# P2B14-001.net
KiCad netlist of a schematic drawn in EAGLE
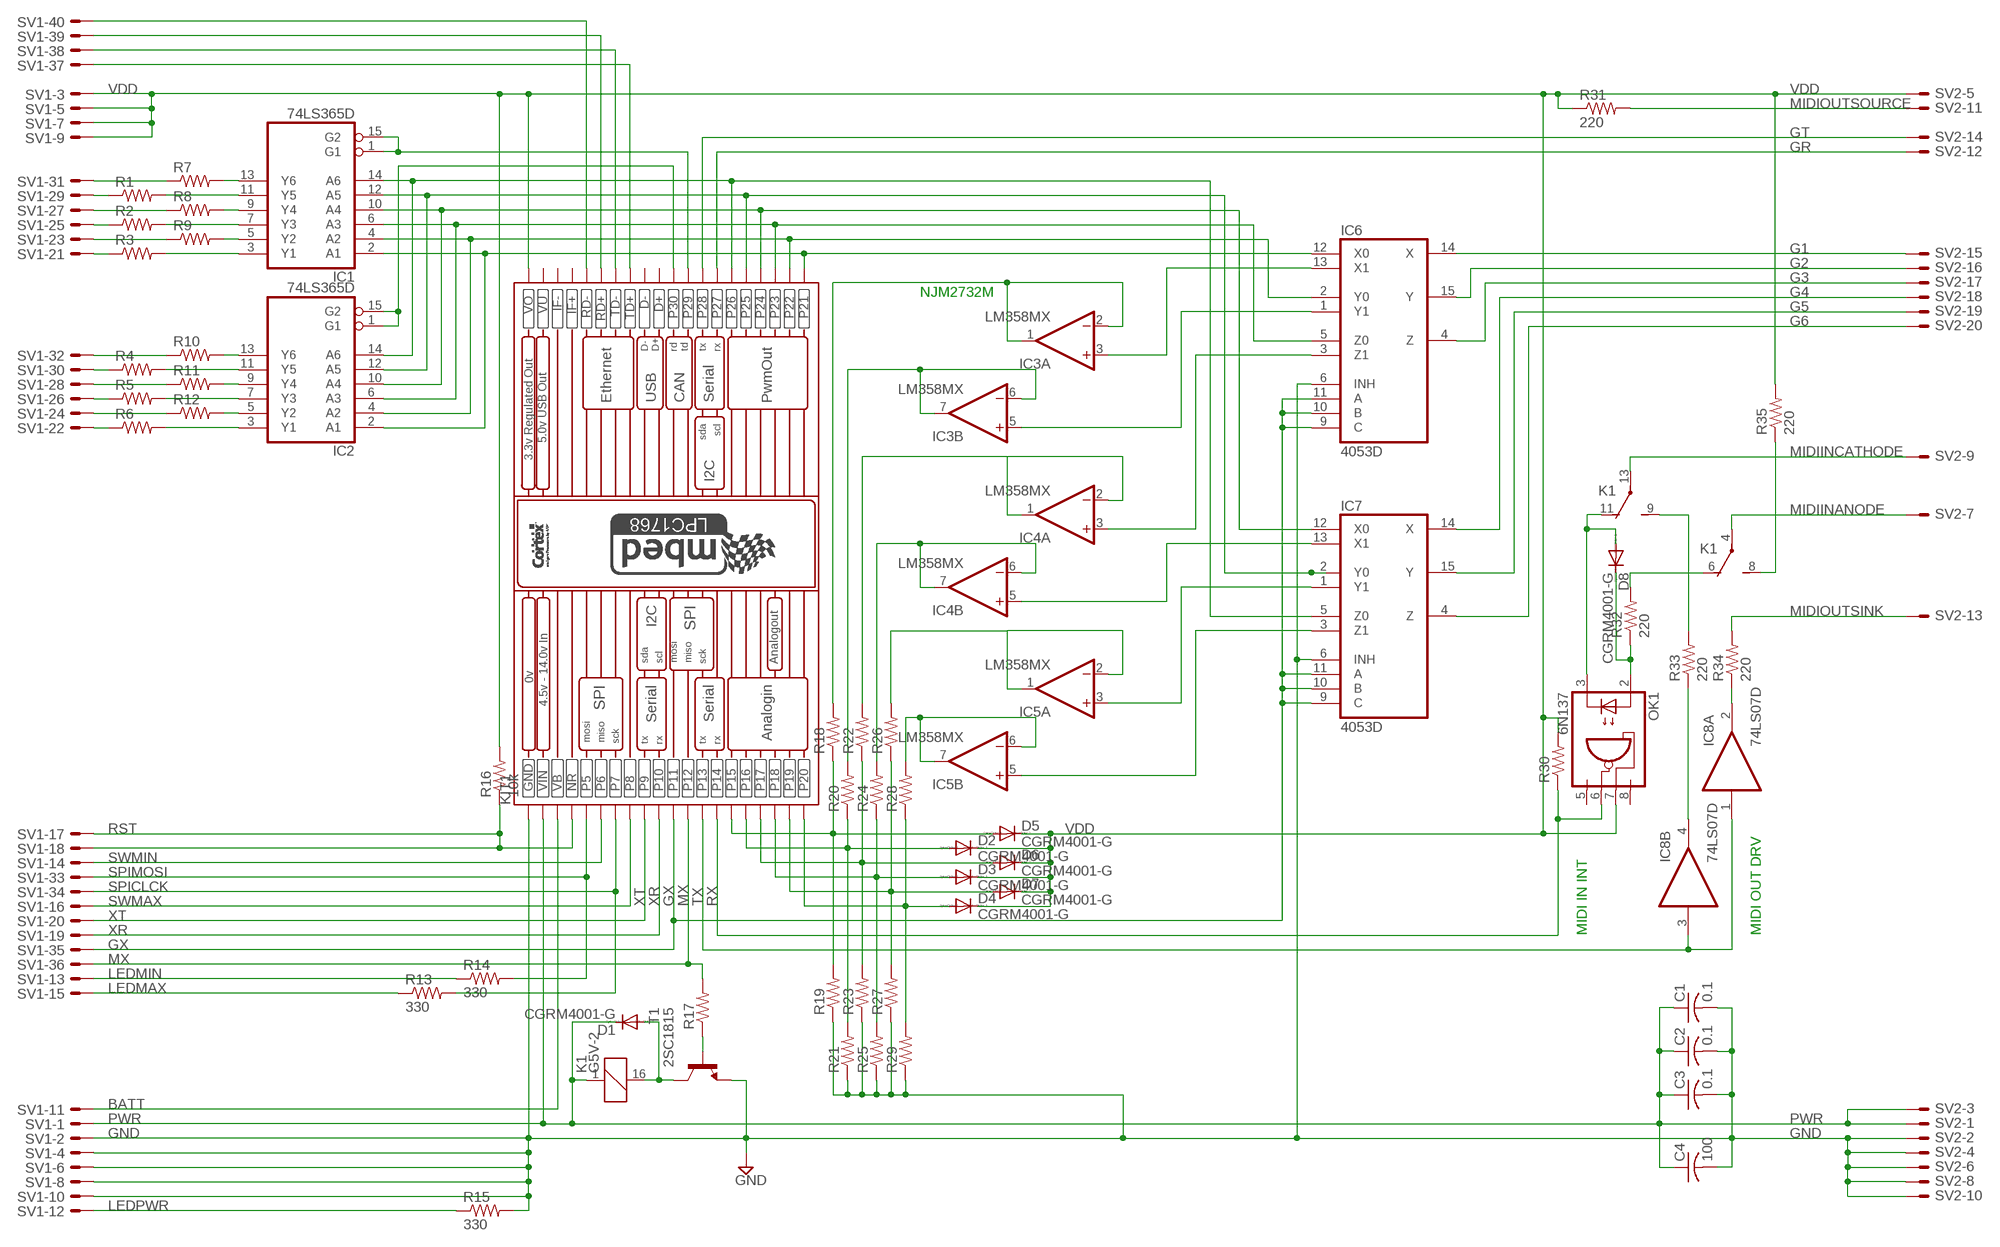
[diagram p0: schematic, sheet 1]

(export (version "E")
  (design (tool "Eeschema 10.0.6"))
  (components
    (comp (ref "C1")
      (value "0.1")
      (footprint "eagle-import:C0402")
      (libsource (lib "eagle-import") (part "C-USC0402"))
    )
    (comp (ref "C2")
      (value "0.1")
      (footprint "eagle-import:C0402")
      (libsource (lib "eagle-import") (part "C-USC0402"))
    )
    (comp (ref "C3")
      (value "0.1")
      (footprint "eagle-import:C0402")
      (libsource (lib "eagle-import") (part "C-USC0402"))
    )
    (comp (ref "C4")
      (value "100")
      (footprint "eagle-import:C025-050X050")
      (libsource (lib "eagle-import") (part "C-US025-050X050"))
    )
    (comp (ref "D1")
      (value "CGRM4001-G")
      (footprint "eagle-import:SOD-123_MINI-SMA")
      (libsource (lib "eagle-import") (part "CGRM400-G1"))
    )
    (comp (ref "D2")
      (value "CGRM4001-G")
      (footprint "eagle-import:SOD-123_MINI-SMA")
      (libsource (lib "eagle-import") (part "CGRM400-G1"))
    )
    (comp (ref "D3")
      (value "CGRM4001-G")
      (footprint "eagle-import:SOD-123_MINI-SMA")
      (libsource (lib "eagle-import") (part "CGRM400-G1"))
    )
    (comp (ref "D4")
      (value "CGRM4001-G")
      (footprint "eagle-import:SOD-123_MINI-SMA")
      (libsource (lib "eagle-import") (part "CGRM400-G1"))
    )
    (comp (ref "D5")
      (value "CGRM4001-G")
      (footprint "eagle-import:SOD-123_MINI-SMA")
      (libsource (lib "eagle-import") (part "CGRM400-G1"))
    )
    (comp (ref "D6")
      (value "CGRM4001-G")
      (footprint "eagle-import:SOD-123_MINI-SMA")
      (libsource (lib "eagle-import") (part "CGRM400-G1"))
    )
    (comp (ref "D7")
      (value "CGRM4001-G")
      (footprint "eagle-import:SOD-123_MINI-SMA")
      (libsource (lib "eagle-import") (part "CGRM400-G1"))
    )
    (comp (ref "D8")
      (value "CGRM4001-G")
      (footprint "eagle-import:SOD-123_MINI-SMA")
      (libsource (lib "eagle-import") (part "CGRM400-G1"))
    )
    (comp (ref "IC1")
      (value "74LS365D")
      (footprint "eagle-import:SO16")
      (libsource (lib "eagle-import") (part "74365DLS"))
    )
    (comp (ref "IC2")
      (value "74LS365D")
      (footprint "eagle-import:SO16")
      (libsource (lib "eagle-import") (part "74365DLS"))
    )
    (comp (ref "IC3")
      (value "LM358MX")
      (footprint "eagle-import:SO08")
      (libsource (lib "eagle-import") (part "LM358MX"))
    )
    (comp (ref "IC4")
      (value "LM358MX")
      (footprint "eagle-import:SO08")
      (libsource (lib "eagle-import") (part "LM358MX"))
    )
    (comp (ref "IC5")
      (value "LM358MX")
      (footprint "eagle-import:SO08")
      (libsource (lib "eagle-import") (part "LM358MX"))
    )
    (comp (ref "IC6")
      (value "4053D")
      (footprint "eagle-import:SO16")
      (libsource (lib "eagle-import") (part "4053D"))
    )
    (comp (ref "IC7")
      (value "4053D")
      (footprint "eagle-import:SO16")
      (libsource (lib "eagle-import") (part "4053D"))
    )
    (comp (ref "IC8")
      (value "74LS07D")
      (footprint "eagle-import:SO14")
      (libsource (lib "eagle-import") (part "7407DLS"))
    )
    (comp (ref "K1")
      (value "G5V-2")
      (footprint "eagle-import:G5V-2")
      (fields (field (name "MPN") "G5V-2 5DC"))
      (libsource (lib "eagle-import") (part "G5V-2"))
    )
    (comp (ref "KIT1")
      (value "MBED_NXP_LPC1768")
      (footprint "eagle-import:MBED-KIT")
      (libsource (lib "eagle-import") (part "MBED_NXP_LPC1768"))
    )
    (comp (ref "OK1")
      (value "6N137")
      (footprint "eagle-import:DIL08")
      (libsource (lib "eagle-import") (part "6N137"))
    )
    (comp (ref "R1")
      (value "R-US_M0805")
      (footprint "eagle-import:M0805")
      (libsource (lib "eagle-import") (part "R-US_M0805"))
    )
    (comp (ref "R2")
      (value "R-US_M0805")
      (footprint "eagle-import:M0805")
      (libsource (lib "eagle-import") (part "R-US_M0805"))
    )
    (comp (ref "R3")
      (value "R-US_M0805")
      (footprint "eagle-import:M0805")
      (libsource (lib "eagle-import") (part "R-US_M0805"))
    )
    (comp (ref "R4")
      (value "R-US_M0805")
      (footprint "eagle-import:M0805")
      (libsource (lib "eagle-import") (part "R-US_M0805"))
    )
    (comp (ref "R5")
      (value "R-US_M0805")
      (footprint "eagle-import:M0805")
      (libsource (lib "eagle-import") (part "R-US_M0805"))
    )
    (comp (ref "R6")
      (value "R-US_M0805")
      (footprint "eagle-import:M0805")
      (libsource (lib "eagle-import") (part "R-US_M0805"))
    )
    (comp (ref "R7")
      (value "R-US_M0805")
      (footprint "eagle-import:M0805")
      (libsource (lib "eagle-import") (part "R-US_M0805"))
    )
    (comp (ref "R8")
      (value "R-US_M0805")
      (footprint "eagle-import:M0805")
      (libsource (lib "eagle-import") (part "R-US_M0805"))
    )
    (comp (ref "R9")
      (value "R-US_M0805")
      (footprint "eagle-import:M0805")
      (libsource (lib "eagle-import") (part "R-US_M0805"))
    )
    (comp (ref "R10")
      (value "R-US_M0805")
      (footprint "eagle-import:M0805")
      (libsource (lib "eagle-import") (part "R-US_M0805"))
    )
    (comp (ref "R11")
      (value "R-US_M0805")
      (footprint "eagle-import:M0805")
      (libsource (lib "eagle-import") (part "R-US_M0805"))
    )
    (comp (ref "R12")
      (value "R-US_M0805")
      (footprint "eagle-import:M0805")
      (libsource (lib "eagle-import") (part "R-US_M0805"))
    )
    (comp (ref "R13")
      (value "330")
      (footprint "eagle-import:M0805")
      (libsource (lib "eagle-import") (part "R-US_M0805"))
    )
    (comp (ref "R14")
      (value "330")
      (footprint "eagle-import:M0805")
      (libsource (lib "eagle-import") (part "R-US_M0805"))
    )
    (comp (ref "R15")
      (value "330")
      (footprint "eagle-import:M0805")
      (libsource (lib "eagle-import") (part "R-US_M0805"))
    )
    (comp (ref "R16")
      (value "10k")
      (footprint "eagle-import:M0805")
      (libsource (lib "eagle-import") (part "R-US_M0805"))
    )
    (comp (ref "R17")
      (value "R-US_M0805")
      (footprint "eagle-import:M0805")
      (libsource (lib "eagle-import") (part "R-US_M0805"))
    )
    (comp (ref "R18")
      (value "R-US_M0805")
      (footprint "eagle-import:M0805")
      (libsource (lib "eagle-import") (part "R-US_M0805"))
    )
    (comp (ref "R19")
      (value "R-US_M0805")
      (footprint "eagle-import:M0805")
      (libsource (lib "eagle-import") (part "R-US_M0805"))
    )
    (comp (ref "R20")
      (value "R-US_M0805")
      (footprint "eagle-import:M0805")
      (libsource (lib "eagle-import") (part "R-US_M0805"))
    )
    (comp (ref "R21")
      (value "R-US_M0805")
      (footprint "eagle-import:M0805")
      (libsource (lib "eagle-import") (part "R-US_M0805"))
    )
    (comp (ref "R22")
      (value "R-US_M0805")
      (footprint "eagle-import:M0805")
      (libsource (lib "eagle-import") (part "R-US_M0805"))
    )
    (comp (ref "R23")
      (value "R-US_M0805")
      (footprint "eagle-import:M0805")
      (libsource (lib "eagle-import") (part "R-US_M0805"))
    )
    (comp (ref "R24")
      (value "R-US_M0805")
      (footprint "eagle-import:M0805")
      (libsource (lib "eagle-import") (part "R-US_M0805"))
    )
    (comp (ref "R25")
      (value "R-US_M0805")
      (footprint "eagle-import:M0805")
      (libsource (lib "eagle-import") (part "R-US_M0805"))
    )
    (comp (ref "R26")
      (value "R-US_M0805")
      (footprint "eagle-import:M0805")
      (libsource (lib "eagle-import") (part "R-US_M0805"))
    )
    (comp (ref "R27")
      (value "R-US_M0805")
      (footprint "eagle-import:M0805")
      (libsource (lib "eagle-import") (part "R-US_M0805"))
    )
    (comp (ref "R28")
      (value "R-US_M0805")
      (footprint "eagle-import:M0805")
      (libsource (lib "eagle-import") (part "R-US_M0805"))
    )
    (comp (ref "R29")
      (value "R-US_M0805")
      (footprint "eagle-import:M0805")
      (libsource (lib "eagle-import") (part "R-US_M0805"))
    )
    (comp (ref "R30")
      (value "R-US_M0805")
      (footprint "eagle-import:M0805")
      (libsource (lib "eagle-import") (part "R-US_M0805"))
    )
    (comp (ref "R31")
      (value "220")
      (footprint "eagle-import:M0805")
      (libsource (lib "eagle-import") (part "R-US_M0805"))
    )
    (comp (ref "R32")
      (value "220")
      (footprint "eagle-import:M0805")
      (libsource (lib "eagle-import") (part "R-US_M0805"))
    )
    (comp (ref "R33")
      (value "220")
      (footprint "eagle-import:M0805")
      (libsource (lib "eagle-import") (part "R-US_M0805"))
    )
    (comp (ref "R34")
      (value "220")
      (footprint "eagle-import:M0805")
      (libsource (lib "eagle-import") (part "R-US_M0805"))
    )
    (comp (ref "R35")
      (value "220")
      (footprint "eagle-import:M0805")
      (libsource (lib "eagle-import") (part "R-US_M0805"))
    )
    (comp (ref "SV1")
      (value "ML40E")
      (footprint "eagle-import:ML40")
      (libsource (lib "eagle-import") (part "ML40E"))
    )
    (comp (ref "SV2")
      (value "ML20LE")
      (footprint "eagle-import:ML20L")
      (libsource (lib "eagle-import") (part "ML20LE"))
    )
    (comp (ref "T1")
      (value "2SC1815")
      (footprint "eagle-import:TO92-ECB")
      (libsource (lib "eagle-import") (part "2SC1815"))
    )
  )
  (nets
    (net (code "1") (name "/BATT") (class "Default")
      (node (ref "KIT1") (pin "VB") (pinfunction "VB_VB") (pintype "power_in"))
      (node (ref "SV1") (pin "11") (pinfunction "S_11") (pintype "passive"))
    )
    (net (code "2") (name "/G1") (class "Default")
      (node (ref "IC6") (pin "14") (pinfunction "X_14") (pintype "bidirectional"))
      (node (ref "SV2") (pin "15") (pinfunction "S_15") (pintype "passive"))
    )
    (net (code "3") (name "/G2") (class "Default")
      (node (ref "IC6") (pin "15") (pinfunction "Y_15") (pintype "bidirectional"))
      (node (ref "SV2") (pin "16") (pinfunction "S_16") (pintype "passive"))
    )
    (net (code "4") (name "/G3") (class "Default")
      (node (ref "IC6") (pin "4") (pinfunction "Z_4") (pintype "bidirectional"))
      (node (ref "SV2") (pin "17") (pinfunction "S_17") (pintype "passive"))
    )
    (net (code "5") (name "/G4") (class "Default")
      (node (ref "IC7") (pin "14") (pinfunction "X_14") (pintype "bidirectional"))
      (node (ref "SV2") (pin "18") (pinfunction "S_18") (pintype "passive"))
    )
    (net (code "6") (name "/G5") (class "Default")
      (node (ref "IC7") (pin "15") (pinfunction "Y_15") (pintype "bidirectional"))
      (node (ref "SV2") (pin "19") (pinfunction "S_19") (pintype "passive"))
    )
    (net (code "7") (name "/G6") (class "Default")
      (node (ref "IC7") (pin "4") (pinfunction "Z_4") (pintype "bidirectional"))
      (node (ref "SV2") (pin "20") (pinfunction "S_20") (pintype "passive"))
    )
    (net (code "8") (name "/GR") (class "Default")
      (node (ref "KIT1") (pin "P$27") (pinfunction "P27_P$27") (pintype "bidirectional"))
      (node (ref "SV2") (pin "12") (pinfunction "S_12") (pintype "passive"))
    )
    (net (code "9") (name "/GT") (class "Default")
      (node (ref "KIT1") (pin "P$28") (pinfunction "P28_P$28") (pintype "bidirectional"))
      (node (ref "SV2") (pin "14") (pinfunction "S_14") (pintype "passive"))
    )
    (net (code "10") (name "/GX") (class "Default")
      (node (ref "IC6") (pin "10") (pinfunction "B_10") (pintype "input"))
      (node (ref "IC6") (pin "11") (pinfunction "A_11") (pintype "input"))
      (node (ref "IC6") (pin "9") (pinfunction "C_9") (pintype "input"))
      (node (ref "IC7") (pin "10") (pinfunction "B_10") (pintype "input"))
      (node (ref "IC7") (pin "11") (pinfunction "A_11") (pintype "input"))
      (node (ref "IC7") (pin "9") (pinfunction "C_9") (pintype "input"))
      (node (ref "KIT1") (pin "P$11") (pinfunction "P11_P$11") (pintype "bidirectional"))
      (node (ref "SV1") (pin "35") (pinfunction "S_35") (pintype "passive"))
    )
    (net (code "11") (name "/LEDMAX") (class "Default")
      (node (ref "R13") (pin "1") (pinfunction "1_1") (pintype "passive"))
      (node (ref "SV1") (pin "15") (pinfunction "S_15") (pintype "passive"))
    )
    (net (code "12") (name "/LEDMIN") (class "Default")
      (node (ref "R14") (pin "1") (pinfunction "1_1") (pintype "passive"))
      (node (ref "SV1") (pin "13") (pinfunction "S_13") (pintype "passive"))
    )
    (net (code "13") (name "/LEDPWR") (class "Default")
      (node (ref "R15") (pin "1") (pinfunction "1_1") (pintype "passive"))
      (node (ref "SV1") (pin "12") (pinfunction "S_12") (pintype "passive"))
    )
    (net (code "14") (name "/MIDIINANODE") (class "Default")
      (node (ref "K1") (pin "4") (pinfunction "P_4") (pintype "passive"))
      (node (ref "SV2") (pin "7") (pinfunction "S_7") (pintype "passive"))
    )
    (net (code "15") (name "/MIDIINCATHODE") (class "Default")
      (node (ref "K1") (pin "13") (pinfunction "P_13") (pintype "passive"))
      (node (ref "SV2") (pin "9") (pinfunction "S_9") (pintype "passive"))
    )
    (net (code "16") (name "/MIDIOUTSINK") (class "Default")
      (node (ref "R34") (pin "2") (pinfunction "2_2") (pintype "passive"))
      (node (ref "SV2") (pin "13") (pinfunction "S_13") (pintype "passive"))
    )
    (net (code "17") (name "/MIDIOUTSOURCE") (class "Default")
      (node (ref "R31") (pin "2") (pinfunction "2_2") (pintype "passive"))
      (node (ref "SV2") (pin "11") (pinfunction "S_11") (pintype "passive"))
    )
    (net (code "18") (name "/MX") (class "Default")
      (node (ref "KIT1") (pin "P$12") (pinfunction "P12_P$12") (pintype "bidirectional"))
      (node (ref "R17") (pin "2") (pinfunction "2_2") (pintype "passive"))
      (node (ref "SV1") (pin "36") (pinfunction "S_36") (pintype "passive"))
    )
    (net (code "19") (name "/PWR") (class "Default")
      (node (ref "C1") (pin "1") (pinfunction "1_1") (pintype "passive"))
      (node (ref "C2") (pin "1") (pinfunction "1_1") (pintype "passive"))
      (node (ref "C3") (pin "1") (pinfunction "1_1") (pintype "passive"))
      (node (ref "C4") (pin "1") (pinfunction "1_1") (pintype "passive"))
      (node (ref "D1") (pin "C") (pinfunction "C_C") (pintype "passive"))
      (node (ref "K1") (pin "1") (pinfunction "1_1") (pintype "passive"))
      (node (ref "KIT1") (pin "VIN") (pinfunction "VIN_VIN") (pintype "power_in"))
      (node (ref "SV1") (pin "1") (pinfunction "S_1") (pintype "passive"))
      (node (ref "SV2") (pin "1") (pinfunction "S_1") (pintype "passive"))
      (node (ref "SV2") (pin "3") (pinfunction "S_3") (pintype "passive"))
    )
    (net (code "20") (name "/RST") (class "Default")
      (node (ref "KIT1") (pin "NR") (pinfunction "NR_NR") (pintype "power_in"))
      (node (ref "R16") (pin "1") (pinfunction "1_1") (pintype "passive"))
      (node (ref "SV1") (pin "17") (pinfunction "S_17") (pintype "passive"))
      (node (ref "SV1") (pin "18") (pinfunction "S_18") (pintype "passive"))
    )
    (net (code "21") (name "/RX") (class "Default")
      (node (ref "KIT1") (pin "P$14") (pinfunction "P14_P$14") (pintype "bidirectional"))
      (node (ref "OK1") (pin "6") (pinfunction "VO_6") (pintype "passive"))
      (node (ref "R30") (pin "1") (pinfunction "1_1") (pintype "passive"))
    )
    (net (code "22") (name "/SPICLCK") (class "Default")
      (node (ref "KIT1") (pin "P$7") (pinfunction "P7_P$7") (pintype "bidirectional"))
      (node (ref "R13") (pin "2") (pinfunction "2_2") (pintype "passive"))
      (node (ref "SV1") (pin "34") (pinfunction "S_34") (pintype "passive"))
    )
    (net (code "23") (name "/SPIMOSI") (class "Default")
      (node (ref "KIT1") (pin "P$5") (pinfunction "P5_P$5") (pintype "bidirectional"))
      (node (ref "R14") (pin "2") (pinfunction "2_2") (pintype "passive"))
      (node (ref "SV1") (pin "33") (pinfunction "S_33") (pintype "passive"))
    )
    (net (code "24") (name "/SWMAX") (class "Default")
      (node (ref "KIT1") (pin "P$8") (pinfunction "P8_P$8") (pintype "bidirectional"))
      (node (ref "SV1") (pin "16") (pinfunction "S_16") (pintype "passive"))
    )
    (net (code "25") (name "/SWMIN") (class "Default")
      (node (ref "KIT1") (pin "P$6") (pinfunction "P6_P$6") (pintype "bidirectional"))
      (node (ref "SV1") (pin "14") (pinfunction "S_14") (pintype "passive"))
    )
    (net (code "26") (name "/TX") (class "Default")
      (node (ref "IC8") (pin "1") (pinfunction "I_1") (pintype "input"))
      (node (ref "IC8") (pin "3") (pinfunction "I_3") (pintype "input"))
      (node (ref "KIT1") (pin "P$13") (pinfunction "P13_P$13") (pintype "bidirectional"))
    )
    (net (code "27") (name "/VDD") (class "Default")
      (node (ref "D2") (pin "C") (pinfunction "C_C") (pintype "passive"))
      (node (ref "D3") (pin "C") (pinfunction "C_C") (pintype "passive"))
      (node (ref "D4") (pin "C") (pinfunction "C_C") (pintype "passive"))
      (node (ref "D5") (pin "C") (pinfunction "C_C") (pintype "passive"))
      (node (ref "D6") (pin "C") (pinfunction "C_C") (pintype "passive"))
      (node (ref "D7") (pin "C") (pinfunction "C_C") (pintype "passive"))
      (node (ref "KIT1") (pin "VOUT") (pinfunction "VO_VOUT") (pintype "power_in"))
      (node (ref "OK1") (pin "7") (pinfunction "VE_7") (pintype "passive"))
      (node (ref "R16") (pin "2") (pinfunction "2_2") (pintype "passive"))
      (node (ref "R30") (pin "2") (pinfunction "2_2") (pintype "passive"))
      (node (ref "R31") (pin "1") (pinfunction "1_1") (pintype "passive"))
      (node (ref "R35") (pin "2") (pinfunction "2_2") (pintype "passive"))
      (node (ref "SV1") (pin "3") (pinfunction "S_3") (pintype "passive"))
      (node (ref "SV1") (pin "5") (pinfunction "S_5") (pintype "passive"))
      (node (ref "SV1") (pin "7") (pinfunction "S_7") (pintype "passive"))
      (node (ref "SV1") (pin "9") (pinfunction "S_9") (pintype "passive"))
      (node (ref "SV2") (pin "5") (pinfunction "S_5") (pintype "passive"))
    )
    (net (code "28") (name "/VU") (class "Default")
      (node (ref "KIT1") (pin "VU") (pinfunction "VU_VU") (pintype "power_in"))
    )
    (net (code "29") (name "/XR") (class "Default")
      (node (ref "KIT1") (pin "P$10") (pinfunction "P10_P$10") (pintype "bidirectional"))
      (node (ref "SV1") (pin "19") (pinfunction "S_19") (pintype "passive"))
    )
    (net (code "30") (name "/XT") (class "Default")
      (node (ref "KIT1") (pin "P$9") (pinfunction "P9_P$9") (pintype "bidirectional"))
      (node (ref "SV1") (pin "20") (pinfunction "S_20") (pintype "passive"))
    )
    (net (code "31") (name "GND") (class "Default")
      (node (ref "C1") (pin "2") (pinfunction "2_2") (pintype "passive"))
      (node (ref "C2") (pin "2") (pinfunction "2_2") (pintype "passive"))
      (node (ref "C3") (pin "2") (pinfunction "2_2") (pintype "passive"))
      (node (ref "C4") (pin "2") (pinfunction "2_2") (pintype "passive"))
      (node (ref "IC6") (pin "6") (pinfunction "INH_6") (pintype "input"))
      (node (ref "IC7") (pin "6") (pinfunction "INH_6") (pintype "input"))
      (node (ref "KIT1") (pin "GND") (pinfunction "GND_GND") (pintype "power_in"))
      (node (ref "R15") (pin "2") (pinfunction "2_2") (pintype "passive"))
      (node (ref "R19") (pin "1") (pinfunction "1_1") (pintype "passive"))
      (node (ref "R21") (pin "1") (pinfunction "1_1") (pintype "passive"))
      (node (ref "R23") (pin "1") (pinfunction "1_1") (pintype "passive"))
      (node (ref "R25") (pin "1") (pinfunction "1_1") (pintype "passive"))
      (node (ref "R27") (pin "1") (pinfunction "1_1") (pintype "passive"))
      (node (ref "R29") (pin "1") (pinfunction "1_1") (pintype "passive"))
      (node (ref "SV1") (pin "10") (pinfunction "S_10") (pintype "passive"))
      (node (ref "SV1") (pin "2") (pinfunction "S_2") (pintype "passive"))
      (node (ref "SV1") (pin "4") (pinfunction "S_4") (pintype "passive"))
      (node (ref "SV1") (pin "6") (pinfunction "S_6") (pintype "passive"))
      (node (ref "SV1") (pin "8") (pinfunction "S_8") (pintype "passive"))
      (node (ref "SV2") (pin "10") (pinfunction "S_10") (pintype "passive"))
      (node (ref "SV2") (pin "2") (pinfunction "S_2") (pintype "passive"))
      (node (ref "SV2") (pin "4") (pinfunction "S_4") (pintype "passive"))
      (node (ref "SV2") (pin "6") (pinfunction "S_6") (pintype "passive"))
      (node (ref "SV2") (pin "8") (pinfunction "S_8") (pintype "passive"))
      (node (ref "T1") (pin "E") (pinfunction "E_E") (pintype "passive"))
    )
    (net (code "32") (name "Net-(IC1A-A1)") (class "Default")
      (node (ref "IC1") (pin "2") (pinfunction "A1_2") (pintype "input"))
      (node (ref "IC2") (pin "2") (pinfunction "A1_2") (pintype "input"))
      (node (ref "IC6") (pin "12") (pinfunction "X0_12") (pintype "bidirectional"))
      (node (ref "KIT1") (pin "P$21") (pinfunction "P21_P$21") (pintype "bidirectional"))
    )
    (net (code "33") (name "Net-(IC1A-A2)") (class "Default")
      (node (ref "IC1") (pin "4") (pinfunction "A2_4") (pintype "input"))
      (node (ref "IC2") (pin "4") (pinfunction "A2_4") (pintype "input"))
      (node (ref "IC6") (pin "2") (pinfunction "Y0_2") (pintype "bidirectional"))
      (node (ref "KIT1") (pin "P$22") (pinfunction "P22_P$22") (pintype "bidirectional"))
    )
    (net (code "34") (name "Net-(IC1A-A3)") (class "Default")
      (node (ref "IC1") (pin "6") (pinfunction "A3_6") (pintype "input"))
      (node (ref "IC2") (pin "6") (pinfunction "A3_6") (pintype "input"))
      (node (ref "IC6") (pin "5") (pinfunction "Z0_5") (pintype "bidirectional"))
      (node (ref "KIT1") (pin "P$23") (pinfunction "P23_P$23") (pintype "bidirectional"))
    )
    (net (code "35") (name "Net-(IC1A-A4)") (class "Default")
      (node (ref "IC1") (pin "10") (pinfunction "A4_10") (pintype "input"))
      (node (ref "IC2") (pin "10") (pinfunction "A4_10") (pintype "input"))
      (node (ref "IC7") (pin "12") (pinfunction "X0_12") (pintype "bidirectional"))
      (node (ref "KIT1") (pin "P$24") (pinfunction "P24_P$24") (pintype "bidirectional"))
    )
    (net (code "36") (name "Net-(IC1A-A5)") (class "Default")
      (node (ref "IC1") (pin "12") (pinfunction "A5_12") (pintype "input"))
      (node (ref "IC2") (pin "12") (pinfunction "A5_12") (pintype "input"))
      (node (ref "IC7") (pin "2") (pinfunction "Y0_2") (pintype "bidirectional"))
      (node (ref "KIT1") (pin "P$25") (pinfunction "P25_P$25") (pintype "bidirectional"))
    )
    (net (code "37") (name "Net-(IC1A-A6)") (class "Default")
      (node (ref "IC1") (pin "14") (pinfunction "A6_14") (pintype "input"))
      (node (ref "IC2") (pin "14") (pinfunction "A6_14") (pintype "input"))
      (node (ref "IC7") (pin "5") (pinfunction "Z0_5") (pintype "bidirectional"))
      (node (ref "KIT1") (pin "P$26") (pinfunction "P26_P$26") (pintype "bidirectional"))
    )
    (net (code "38") (name "Net-(IC1A-G1)") (class "Default")
      (node (ref "IC1") (pin "1") (pinfunction "G1_1") (pintype "input"))
      (node (ref "IC1") (pin "15") (pinfunction "G2_15") (pintype "input"))
      (node (ref "KIT1") (pin "P$29") (pinfunction "P29_P$29") (pintype "bidirectional"))
    )
    (net (code "39") (name "Net-(IC1A-Y1)") (class "Default")
      (node (ref "IC1") (pin "3") (pinfunction "Y1_3") (pintype "tri_state"))
      (node (ref "R3") (pin "2") (pinfunction "2_2") (pintype "passive"))
    )
    (net (code "40") (name "Net-(IC1A-Y2)") (class "Default")
      (node (ref "IC1") (pin "5") (pinfunction "Y2_5") (pintype "tri_state"))
      (node (ref "R9") (pin "2") (pinfunction "2_2") (pintype "passive"))
    )
    (net (code "41") (name "Net-(IC1A-Y3)") (class "Default")
      (node (ref "IC1") (pin "7") (pinfunction "Y3_7") (pintype "tri_state"))
      (node (ref "R2") (pin "2") (pinfunction "2_2") (pintype "passive"))
    )
    (net (code "42") (name "Net-(IC1A-Y4)") (class "Default")
      (node (ref "IC1") (pin "9") (pinfunction "Y4_9") (pintype "tri_state"))
      (node (ref "R8") (pin "2") (pinfunction "2_2") (pintype "passive"))
    )
    (net (code "43") (name "Net-(IC1A-Y5)") (class "Default")
      (node (ref "IC1") (pin "11") (pinfunction "Y5_11") (pintype "tri_state"))
      (node (ref "R1") (pin "2") (pinfunction "2_2") (pintype "passive"))
    )
    (net (code "44") (name "Net-(IC1A-Y6)") (class "Default")
      (node (ref "IC1") (pin "13") (pinfunction "Y6_13") (pintype "tri_state"))
      (node (ref "R7") (pin "2") (pinfunction "2_2") (pintype "passive"))
    )
    (net (code "45") (name "Net-(IC2A-G1)") (class "Default")
      (node (ref "IC2") (pin "1") (pinfunction "G1_1") (pintype "input"))
      (node (ref "IC2") (pin "15") (pinfunction "G2_15") (pintype "input"))
      (node (ref "KIT1") (pin "P$30") (pinfunction "P30_P$30") (pintype "bidirectional"))
    )
    (net (code "46") (name "Net-(IC2A-Y1)") (class "Default")
      (node (ref "IC2") (pin "3") (pinfunction "Y1_3") (pintype "tri_state"))
      (node (ref "R6") (pin "2") (pinfunction "2_2") (pintype "passive"))
    )
    (net (code "47") (name "Net-(IC2A-Y2)") (class "Default")
      (node (ref "IC2") (pin "5") (pinfunction "Y2_5") (pintype "tri_state"))
      (node (ref "R12") (pin "2") (pinfunction "2_2") (pintype "passive"))
    )
    (net (code "48") (name "Net-(IC2A-Y3)") (class "Default")
      (node (ref "IC2") (pin "7") (pinfunction "Y3_7") (pintype "tri_state"))
      (node (ref "R5") (pin "2") (pinfunction "2_2") (pintype "passive"))
    )
    (net (code "49") (name "Net-(IC2A-Y4)") (class "Default")
      (node (ref "IC2") (pin "9") (pinfunction "Y4_9") (pintype "tri_state"))
      (node (ref "R11") (pin "2") (pinfunction "2_2") (pintype "passive"))
    )
    (net (code "50") (name "Net-(IC2A-Y5)") (class "Default")
      (node (ref "IC2") (pin "11") (pinfunction "Y5_11") (pintype "tri_state"))
      (node (ref "R4") (pin "2") (pinfunction "2_2") (pintype "passive"))
    )
    (net (code "51") (name "Net-(IC2A-Y6)") (class "Default")
      (node (ref "IC2") (pin "13") (pinfunction "Y6_13") (pintype "tri_state"))
      (node (ref "R10") (pin "2") (pinfunction "2_2") (pintype "passive"))
    )
    (net (code "52") (name "Net-(IC3A-+IN)") (class "Default")
      (node (ref "IC3") (pin "3") (pinfunction "+IN_3") (pintype "input"))
      (node (ref "IC6") (pin "13") (pinfunction "X1_13") (pintype "bidirectional"))
    )
    (net (code "53") (name "Net-(IC3A--IN)") (class "Default")
      (node (ref "IC3") (pin "1") (pinfunction "OUT_1") (pintype "output"))
      (node (ref "IC3") (pin "2") (pinfunction "-IN_2") (pintype "input"))
      (node (ref "R18") (pin "2") (pinfunction "2_2") (pintype "passive"))
    )
    (net (code "54") (name "Net-(IC3B-+IN)") (class "Default")
      (node (ref "IC3") (pin "5") (pinfunction "+IN_5") (pintype "input"))
      (node (ref "IC6") (pin "1") (pinfunction "Y1_1") (pintype "bidirectional"))
    )
    (net (code "55") (name "Net-(IC3B--IN)") (class "Default")
      (node (ref "IC3") (pin "6") (pinfunction "-IN_6") (pintype "input"))
      (node (ref "IC3") (pin "7") (pinfunction "OUT_7") (pintype "output"))
      (node (ref "R20") (pin "2") (pinfunction "2_2") (pintype "passive"))
    )
    (net (code "56") (name "Net-(IC4A-+IN)") (class "Default")
      (node (ref "IC4") (pin "3") (pinfunction "+IN_3") (pintype "input"))
      (node (ref "IC6") (pin "3") (pinfunction "Z1_3") (pintype "bidirectional"))
    )
    (net (code "57") (name "Net-(IC4A--IN)") (class "Default")
      (node (ref "IC4") (pin "1") (pinfunction "OUT_1") (pintype "output"))
      (node (ref "IC4") (pin "2") (pinfunction "-IN_2") (pintype "input"))
      (node (ref "R22") (pin "2") (pinfunction "2_2") (pintype "passive"))
    )
    (net (code "58") (name "Net-(IC4B-+IN)") (class "Default")
      (node (ref "IC4") (pin "5") (pinfunction "+IN_5") (pintype "input"))
      (node (ref "IC7") (pin "13") (pinfunction "X1_13") (pintype "bidirectional"))
    )
    (net (code "59") (name "Net-(IC4B--IN)") (class "Default")
      (node (ref "IC4") (pin "6") (pinfunction "-IN_6") (pintype "input"))
      (node (ref "IC4") (pin "7") (pinfunction "OUT_7") (pintype "output"))
      (node (ref "R24") (pin "2") (pinfunction "2_2") (pintype "passive"))
    )
    (net (code "60") (name "Net-(IC5A-+IN)") (class "Default")
      (node (ref "IC5") (pin "3") (pinfunction "+IN_3") (pintype "input"))
      (node (ref "IC7") (pin "1") (pinfunction "Y1_1") (pintype "bidirectional"))
    )
    (net (code "61") (name "Net-(IC5A--IN)") (class "Default")
      (node (ref "IC5") (pin "1") (pinfunction "OUT_1") (pintype "output"))
      (node (ref "IC5") (pin "2") (pinfunction "-IN_2") (pintype "input"))
      (node (ref "R26") (pin "2") (pinfunction "2_2") (pintype "passive"))
    )
    (net (code "62") (name "Net-(IC5B-+IN)") (class "Default")
      (node (ref "IC5") (pin "5") (pinfunction "+IN_5") (pintype "input"))
      (node (ref "IC7") (pin "3") (pinfunction "Z1_3") (pintype "bidirectional"))
    )
    (net (code "63") (name "Net-(IC5B--IN)") (class "Default")
      (node (ref "IC5") (pin "6") (pinfunction "-IN_6") (pintype "input"))
      (node (ref "IC5") (pin "7") (pinfunction "OUT_7") (pintype "output"))
      (node (ref "R28") (pin "2") (pinfunction "2_2") (pintype "passive"))
    )
    (net (code "64") (name "Net-(IC8A-O)") (class "Default")
      (node (ref "IC8") (pin "2") (pinfunction "O_2") (pintype "open_collector"))
      (node (ref "R34") (pin "1") (pinfunction "1_1") (pintype "passive"))
    )
    (net (code "65") (name "Net-(IC8B-O)") (class "Default")
      (node (ref "IC8") (pin "4") (pinfunction "O_4") (pintype "open_collector"))
      (node (ref "R33") (pin "1") (pinfunction "1_1") (pintype "passive"))
    )
    (net (code "66") (name "Net-(K1A-O)") (class "Default")
      (node (ref "K1") (pin "6") (pinfunction "O_6") (pintype "passive"))
      (node (ref "R32") (pin "2") (pinfunction "2_2") (pintype "passive"))
    )
    (net (code "67") (name "Net-(K1A-S)") (class "Default")
      (node (ref "K1") (pin "8") (pinfunction "S_8") (pintype "passive"))
      (node (ref "R35") (pin "1") (pinfunction "1_1") (pintype "passive"))
    )
    (net (code "68") (name "Net-(K1B-O)") (class "Default")
      (node (ref "D8") (pin "A") (pinfunction "A_A") (pintype "passive"))
      (node (ref "K1") (pin "11") (pinfunction "O_11") (pintype "passive"))
      (node (ref "OK1") (pin "3") (pinfunction "C_3") (pintype "passive"))
    )
    (net (code "69") (name "Net-(K1B-S)") (class "Default")
      (node (ref "K1") (pin "9") (pinfunction "S_9") (pintype "passive"))
      (node (ref "R33") (pin "2") (pinfunction "2_2") (pintype "passive"))
    )
    (net (code "70") (name "Net-(K1C-2)") (class "Default")
      (node (ref "D1") (pin "A") (pinfunction "A_A") (pintype "passive"))
      (node (ref "K1") (pin "16") (pinfunction "2_16") (pintype "passive"))
      (node (ref "T1") (pin "C") (pinfunction "C_C") (pintype "passive"))
    )
    (net (code "71") (name "Net-(KIT1-P15)") (class "Default")
      (node (ref "D5") (pin "A") (pinfunction "A_A") (pintype "passive"))
      (node (ref "KIT1") (pin "P$15") (pinfunction "P15_P$15") (pintype "bidirectional"))
      (node (ref "R18") (pin "1") (pinfunction "1_1") (pintype "passive"))
      (node (ref "R19") (pin "2") (pinfunction "2_2") (pintype "passive"))
    )
    (net (code "72") (name "Net-(KIT1-P16)") (class "Default")
      (node (ref "D2") (pin "A") (pinfunction "A_A") (pintype "passive"))
      (node (ref "KIT1") (pin "P$16") (pinfunction "P16_P$16") (pintype "bidirectional"))
      (node (ref "R20") (pin "1") (pinfunction "1_1") (pintype "passive"))
      (node (ref "R21") (pin "2") (pinfunction "2_2") (pintype "passive"))
    )
    (net (code "73") (name "Net-(KIT1-P17)") (class "Default")
      (node (ref "D6") (pin "A") (pinfunction "A_A") (pintype "passive"))
      (node (ref "KIT1") (pin "P$17") (pinfunction "P17_P$17") (pintype "bidirectional"))
      (node (ref "R22") (pin "1") (pinfunction "1_1") (pintype "passive"))
      (node (ref "R23") (pin "2") (pinfunction "2_2") (pintype "passive"))
    )
    (net (code "74") (name "Net-(KIT1-P18)") (class "Default")
      (node (ref "D3") (pin "A") (pinfunction "A_A") (pintype "passive"))
      (node (ref "KIT1") (pin "P$18") (pinfunction "P18_P$18") (pintype "bidirectional"))
      (node (ref "R24") (pin "1") (pinfunction "1_1") (pintype "passive"))
      (node (ref "R25") (pin "2") (pinfunction "2_2") (pintype "passive"))
    )
    (net (code "75") (name "Net-(KIT1-P19)") (class "Default")
      (node (ref "D7") (pin "A") (pinfunction "A_A") (pintype "passive"))
      (node (ref "KIT1") (pin "P$19") (pinfunction "P19_P$19") (pintype "bidirectional"))
      (node (ref "R26") (pin "1") (pinfunction "1_1") (pintype "passive"))
      (node (ref "R27") (pin "2") (pinfunction "2_2") (pintype "passive"))
    )
    (net (code "76") (name "Net-(KIT1-P20)") (class "Default")
      (node (ref "D4") (pin "A") (pinfunction "A_A") (pintype "passive"))
      (node (ref "KIT1") (pin "P$20") (pinfunction "P20_P$20") (pintype "bidirectional"))
      (node (ref "R28") (pin "1") (pinfunction "1_1") (pintype "passive"))
      (node (ref "R29") (pin "2") (pinfunction "2_2") (pintype "passive"))
    )
    (net (code "77") (name "Net-(OK1-A)") (class "Default")
      (node (ref "D8") (pin "C") (pinfunction "C_C") (pintype "passive"))
      (node (ref "OK1") (pin "2") (pinfunction "A_2") (pintype "passive"))
      (node (ref "R32") (pin "1") (pinfunction "1_1") (pintype "passive"))
    )
    (net (code "78") (name "Net-(R17-Pad1)") (class "Default")
      (node (ref "R17") (pin "1") (pinfunction "1_1") (pintype "passive"))
      (node (ref "T1") (pin "B") (pinfunction "B_B") (pintype "passive"))
    )
    (net (code "79") (name "Net-(SV1AE-S)") (class "Default")
      (node (ref "KIT1") (pin "TD+") (pinfunction "TD+_TD+") (pintype "bidirectional"))
      (node (ref "SV1") (pin "37") (pinfunction "S_37") (pintype "passive"))
    )
    (net (code "80") (name "Net-(SV1AF-S)") (class "Default")
      (node (ref "KIT1") (pin "TD-") (pinfunction "TD-_TD-") (pintype "bidirectional"))
      (node (ref "SV1") (pin "38") (pinfunction "S_38") (pintype "passive"))
    )
    (net (code "81") (name "Net-(SV1AG-S)") (class "Default")
      (node (ref "KIT1") (pin "RD+") (pinfunction "RD+_RD+") (pintype "bidirectional"))
      (node (ref "SV1") (pin "39") (pinfunction "S_39") (pintype "passive"))
    )
    (net (code "82") (name "Net-(SV1AI-S)") (class "Default")
      (node (ref "KIT1") (pin "RD-") (pinfunction "RD-_RD-") (pintype "bidirectional"))
      (node (ref "SV1") (pin "40") (pinfunction "S_40") (pintype "passive"))
    )
    (net (code "83") (name "Net-(SV1N-S)") (class "Default")
      (node (ref "R3") (pin "1") (pinfunction "1_1") (pintype "passive"))
      (node (ref "SV1") (pin "21") (pinfunction "S_21") (pintype "passive"))
    )
    (net (code "84") (name "Net-(SV1O-S)") (class "Default")
      (node (ref "R6") (pin "1") (pinfunction "1_1") (pintype "passive"))
      (node (ref "SV1") (pin "22") (pinfunction "S_22") (pintype "passive"))
    )
    (net (code "85") (name "Net-(SV1P-S)") (class "Default")
      (node (ref "R9") (pin "1") (pinfunction "1_1") (pintype "passive"))
      (node (ref "SV1") (pin "23") (pinfunction "S_23") (pintype "passive"))
    )
    (net (code "86") (name "Net-(SV1Q-S)") (class "Default")
      (node (ref "R12") (pin "1") (pinfunction "1_1") (pintype "passive"))
      (node (ref "SV1") (pin "24") (pinfunction "S_24") (pintype "passive"))
    )
    (net (code "87") (name "Net-(SV1R-S)") (class "Default")
      (node (ref "R2") (pin "1") (pinfunction "1_1") (pintype "passive"))
      (node (ref "SV1") (pin "25") (pinfunction "S_25") (pintype "passive"))
    )
    (net (code "88") (name "Net-(SV1S-S)") (class "Default")
      (node (ref "R5") (pin "1") (pinfunction "1_1") (pintype "passive"))
      (node (ref "SV1") (pin "26") (pinfunction "S_26") (pintype "passive"))
    )
    (net (code "89") (name "Net-(SV1T-S)") (class "Default")
      (node (ref "R8") (pin "1") (pinfunction "1_1") (pintype "passive"))
      (node (ref "SV1") (pin "27") (pinfunction "S_27") (pintype "passive"))
    )
    (net (code "90") (name "Net-(SV1U-S)") (class "Default")
      (node (ref "R11") (pin "1") (pinfunction "1_1") (pintype "passive"))
      (node (ref "SV1") (pin "28") (pinfunction "S_28") (pintype "passive"))
    )
    (net (code "91") (name "Net-(SV1V-S)") (class "Default")
      (node (ref "R1") (pin "1") (pinfunction "1_1") (pintype "passive"))
      (node (ref "SV1") (pin "29") (pinfunction "S_29") (pintype "passive"))
    )
    (net (code "92") (name "Net-(SV1X-S)") (class "Default")
      (node (ref "R4") (pin "1") (pinfunction "1_1") (pintype "passive"))
      (node (ref "SV1") (pin "30") (pinfunction "S_30") (pintype "passive"))
    )
    (net (code "93") (name "Net-(SV1Y-S)") (class "Default")
      (node (ref "R7") (pin "1") (pinfunction "1_1") (pintype "passive"))
      (node (ref "SV1") (pin "31") (pinfunction "S_31") (pintype "passive"))
    )
    (net (code "94") (name "Net-(SV1Z-S)") (class "Default")
      (node (ref "R10") (pin "1") (pinfunction "1_1") (pintype "passive"))
      (node (ref "SV1") (pin "32") (pinfunction "S_32") (pintype "passive"))
    )
    (net (code "95") (name "unconnected-(KIT1-PadD+)") (class "Default")
      (node (ref "KIT1") (pin "D+") (pinfunction "D+_D+") (pintype "bidirectional"))
    )
    (net (code "96") (name "unconnected-(KIT1-PadD-)") (class "Default")
      (node (ref "KIT1") (pin "D-") (pinfunction "D-_D-") (pintype "bidirectional"))
    )
    (net (code "97") (name "unconnected-(KIT1-PadIF+)") (class "Default")
      (node (ref "KIT1") (pin "IF+") (pinfunction "IF+_IF+") (pintype "bidirectional"))
    )
    (net (code "98") (name "unconnected-(KIT1-PadIF-)") (class "Default")
      (node (ref "KIT1") (pin "IF-") (pinfunction "IF-_IF-") (pintype "bidirectional"))
    )
    (net (code "99") (name "unconnected-(OK1-GND-Pad5)") (class "Default")
      (node (ref "OK1") (pin "5") (pinfunction "GND_5") (pintype "passive"))
    )
    (net (code "100") (name "unconnected-(OK1-VCC-Pad8)") (class "Default")
      (node (ref "OK1") (pin "8") (pinfunction "VCC_8") (pintype "passive"))
    )
  )
)
